# UPS_Input_Board.net
KiCad netlist of a schematic drawn in Altium Designer
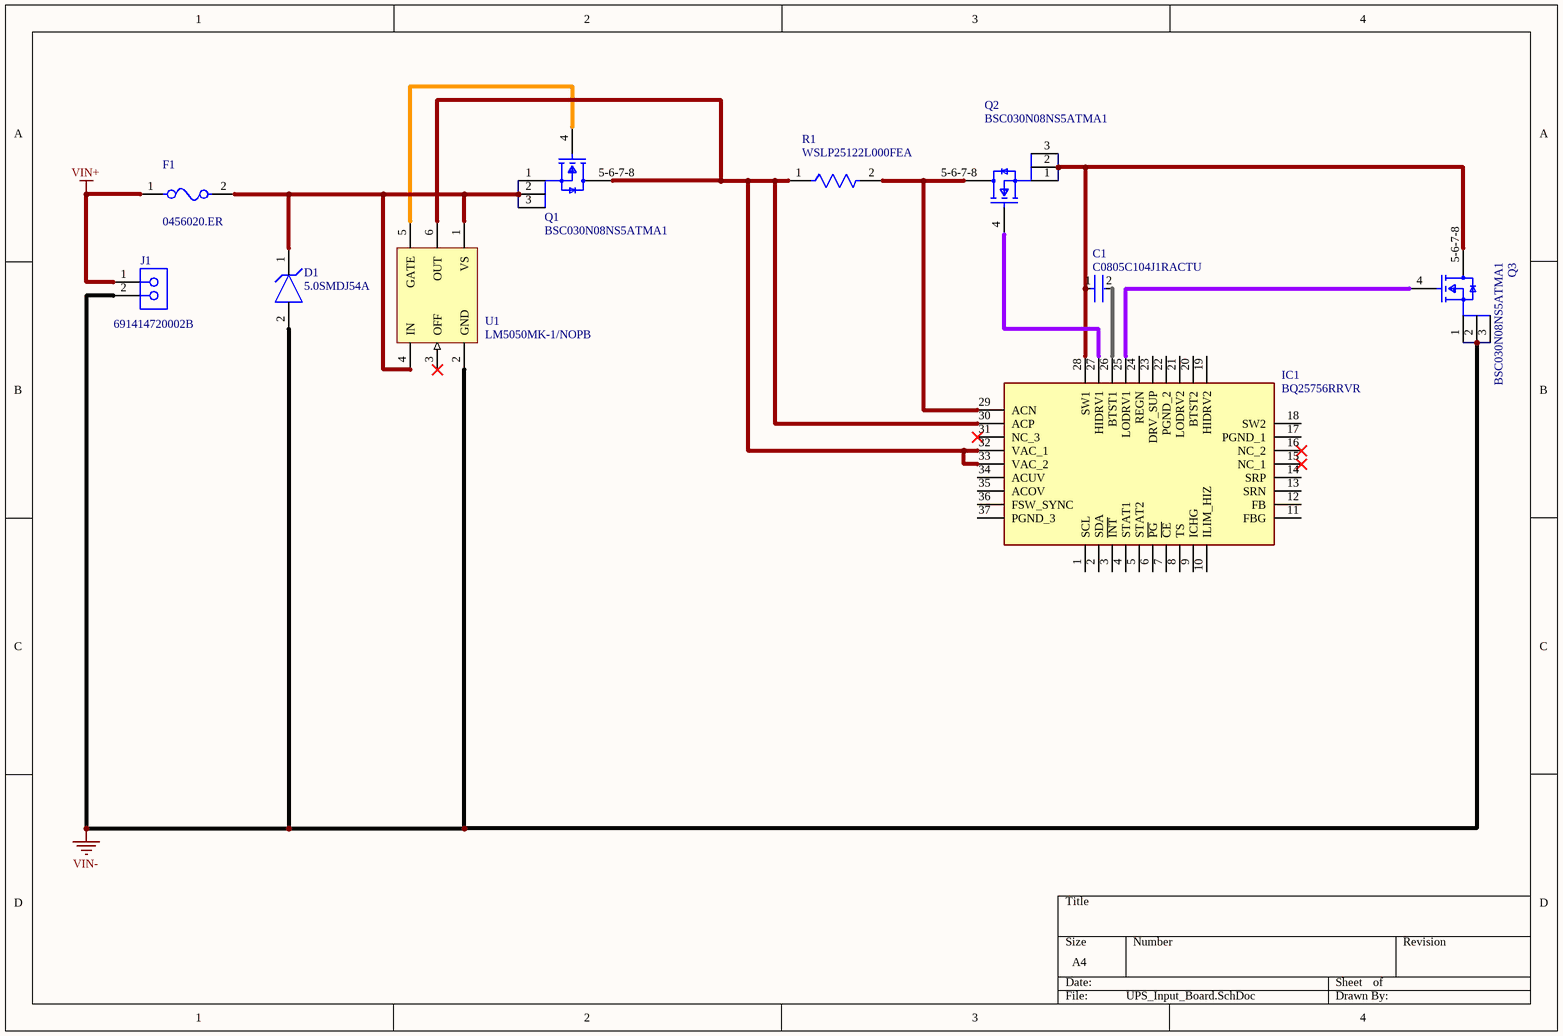
[diagram p0: UPS_Input_Board.SchDoc]

(export (version "E")
  (design (tool "Eeschema 10.0.6"))
  (components
    (comp (ref "C1")
      (value "C0805C104J1RACTU")
      (footprint "FP-C0805C-DN-MFG")
      (description "CAP CER 0.1UF 100V 5% X7R 0805")
      (fields
        (field (name "OCTOPART") "https://octopart.com/c0805c104j1ractu-kemet-10469001")
        (field (name "MANUFACTURER") "KEMET")
      )
      (libsource (lib "Altium Content Vault") (part "b4654b650e69147ec39a6b967a45e02"))
    )
    (comp (ref "D1")
      (value "5.0SMDJ54A")
      (footprint "FP-5_0SMDJ-MFG")
      (description "TVS DIODE 54V 87.1V DO214AB")
      (libsource (lib "Altium Content Vault") (part "673ecd2ea4d7fb87b4005b0cb348b7d"))
    )
    (comp (ref "F1")
      (value "0456020.ER")
      (footprint "FP-0456-MFG")
      (description "FUSE BOARD MNT 20A 125VAC 100VDC")
      (fields
        (field (name "MANUFACTURER") "Littelfuse Inc")
        (field (name "OCTOPART") "https://octopart.com/0456020.er-littelfuse-7502596")
      )
      (libsource (lib "Altium Content Vault") (part "5bcf9b9f640e542cf0359d10258e979"))
    )
    (comp (ref "IC1")
      (value "BQ25756RRVR")
      (footprint "BQ25756RRVR:QFN50P500X600X100-37N-D")
      (description "Integrated Circuit")
      (fields (field (name "MOUSER PART NUMBER") "595-BQ25756RRVR"))
      (libsource (lib "BQ25756RRVR") (part "BQ25756RRVR"))
    )
    (comp (ref "J1")
      (value "691414720002B")
      (footprint "691414720002B")
      (description "Terminal Block, Wtb, 2Way, 28-14Awg Rohs Compliant: Yes")
      (fields (field (name "VOLTAGE") "300V"))
      (libsource (lib "Altium Content Vault") (part "TBL - 1R - 02P - Female"))
    )
    (comp (ref "Q1")
      (value "BSC030N08NS5ATMA1")
      (footprint "FP-PG-TDSON-8-MFG")
      (description "MOSFET N-CH 80V 100A 8TDSON")
      (fields
        (field (name "MANUFACTURER") "Infineon")
        (field (name "OCTOPART") "https://octopart.com/bsc030n08ns5atma1-infineon-52825708")
      )
      (libsource (lib "Altium Content Vault") (part "95ca5d46c4c8fe7d84c4fb5e2abfe3c"))
    )
    (comp (ref "Q2")
      (value "BSC030N08NS5ATMA1")
      (footprint "FP-PG-TDSON-8-MFG")
      (description "MOSFET N-CH 80V 100A 8TDSON")
      (fields
        (field (name "MANUFACTURER") "Infineon")
        (field (name "OCTOPART") "https://octopart.com/bsc030n08ns5atma1-infineon-52825708")
      )
      (libsource (lib "Altium Content Vault") (part "95ca5d46c4c8fe7d84c4fb5e2abfe3c"))
    )
    (comp (ref "Q3")
      (value "BSC030N08NS5ATMA1")
      (footprint "FP-PG-TDSON-8-MFG")
      (description "MOSFET N-CH 80V 100A 8TDSON")
      (fields
        (field (name "MANUFACTURER") "Infineon")
        (field (name "OCTOPART") "https://octopart.com/bsc030n08ns5atma1-infineon-52825708")
      )
      (libsource (lib "Altium Content Vault") (part "95ca5d46c4c8fe7d84c4fb5e2abfe3c"))
    )
    (comp (ref "R1")
      (value "WSLP25122L000FEA")
      (footprint "FP-WSLP2512-0R001-0R0049-MFG")
      (description "RES 0.002 OHM 1% 3W 2512")
      (fields (field (name "TOLERANCE") "1%"))
      (libsource (lib "Altium Content Vault") (part "1029c3af85768c4190bb7ad29bc67b5"))
    )
    (comp (ref "U1")
      (value "LM5050MK-1/NOPB")
      (footprint "DDC0006A_N")
      (description "High Side OR-ing FET Controller, 6-pin TSOT, 1000 Reel")
      (fields (field (name "MANUFACTURER") "Texas Instruments"))
      (libsource (lib "Altium Content Vault") (part "PM-SMPS-LM5050-IL6"))
    )
  )
  (nets
    (net (code "1") (name "Net-(D1-C)") (class "Default")
      (node (ref "D1") (pin "1") (pinfunction "C_1") (pintype "passive"))
      (node (ref "F1") (pin "2") (pinfunction "2_2") (pintype "passive"))
      (node (ref "Q1") (pin "1") (pinfunction "S_1") (pintype "passive"))
      (node (ref "Q1") (pin "2") (pinfunction "S_2") (pintype "passive"))
      (node (ref "Q1") (pin "3") (pinfunction "S_3") (pintype "passive"))
      (node (ref "U1") (pin "1") (pinfunction "VS_1") (pintype "power_in"))
      (node (ref "U1") (pin "4") (pinfunction "IN_4") (pintype "power_in"))
    )
    (net (code "2") (name "Net-(IC1-ACN)") (class "Default")
      (node (ref "IC1") (pin "29") (pinfunction "ACN_29") (pintype "passive"))
      (node (ref "Q2") (pin "5-6-7-8") (pinfunction "D_5-6-7-8") (pintype "passive"))
      (node (ref "R1") (pin "2") (pinfunction "2_2") (pintype "passive"))
    )
    (net (code "3") (name "Net-(IC1-ACP)") (class "Default")
      (node (ref "IC1") (pin "30") (pinfunction "ACP_30") (pintype "passive"))
      (node (ref "IC1") (pin "32") (pinfunction "VAC_1_32") (pintype "passive"))
      (node (ref "IC1") (pin "33") (pinfunction "VAC_2_33") (pintype "passive"))
      (node (ref "Q1") (pin "5-6-7-8") (pinfunction "D_5-6-7-8") (pintype "passive"))
      (node (ref "R1") (pin "1") (pinfunction "1_1") (pintype "passive"))
      (node (ref "U1") (pin "6") (pinfunction "OUT_6") (pintype "power_in"))
    )
    (net (code "4") (name "Net-(IC1-BTST1)") (class "Default")
      (node (ref "C1") (pin "2") (pinfunction "2_2") (pintype "passive"))
      (node (ref "IC1") (pin "26") (pinfunction "BTST1_26") (pintype "passive"))
    )
    (net (code "5") (name "Net-(IC1-HIDRV1)") (class "Default")
      (node (ref "IC1") (pin "27") (pinfunction "HIDRV1_27") (pintype "passive"))
      (node (ref "Q2") (pin "4") (pinfunction "G_4") (pintype "passive"))
    )
    (net (code "6") (name "Net-(IC1-LODRV1)") (class "Default")
      (node (ref "IC1") (pin "25") (pinfunction "LODRV1_25") (pintype "passive"))
      (node (ref "Q3") (pin "4") (pinfunction "G_4") (pintype "passive"))
    )
    (net (code "7") (name "Net-(IC1-SW1)") (class "Default")
      (node (ref "C1") (pin "1") (pinfunction "1_1") (pintype "passive"))
      (node (ref "IC1") (pin "28") (pinfunction "SW1_28") (pintype "passive"))
      (node (ref "Q2") (pin "1") (pinfunction "S_1") (pintype "passive"))
      (node (ref "Q2") (pin "2") (pinfunction "S_2") (pintype "passive"))
      (node (ref "Q2") (pin "3") (pinfunction "S_3") (pintype "passive"))
      (node (ref "Q3") (pin "5-6-7-8") (pinfunction "D_5-6-7-8") (pintype "passive"))
    )
    (net (code "8") (name "Net-(Q1-G)") (class "Default")
      (node (ref "Q1") (pin "4") (pinfunction "G_4") (pintype "passive"))
      (node (ref "U1") (pin "5") (pinfunction "GATE_5") (pintype "power_in"))
    )
    (net (code "9") (name "VIN+") (class "Default")
      (node (ref "F1") (pin "1") (pinfunction "1_1") (pintype "passive"))
      (node (ref "J1") (pin "1") (pinfunction "1_1") (pintype "passive"))
    )
    (net (code "10") (name "VIN-") (class "Default")
      (node (ref "D1") (pin "2") (pinfunction "A_2") (pintype "passive"))
      (node (ref "J1") (pin "2") (pinfunction "2_2") (pintype "passive"))
      (node (ref "Q3") (pin "1") (pinfunction "S_1") (pintype "passive"))
      (node (ref "Q3") (pin "2") (pinfunction "S_2") (pintype "passive"))
      (node (ref "Q3") (pin "3") (pinfunction "S_3") (pintype "passive"))
      (node (ref "U1") (pin "2") (pinfunction "GND_2") (pintype "power_in"))
    )
    (net (code "11") (name "unconnected-(IC1-ACOV-Pad35)") (class "Default")
      (node (ref "IC1") (pin "35") (pinfunction "ACOV_35") (pintype "passive"))
    )
    (net (code "12") (name "unconnected-(IC1-ACUV-Pad34)") (class "Default")
      (node (ref "IC1") (pin "34") (pinfunction "ACUV_34") (pintype "passive"))
    )
    (net (code "13") (name "unconnected-(IC1-BTST2-Pad20)") (class "Default")
      (node (ref "IC1") (pin "20") (pinfunction "BTST2_20") (pintype "passive"))
    )
    (net (code "14") (name "unconnected-(IC1-DRV_SUP-Pad23)") (class "Default")
      (node (ref "IC1") (pin "23") (pinfunction "DRV_SUP_23") (pintype "passive"))
    )
    (net (code "15") (name "unconnected-(IC1-FB-Pad12)") (class "Default")
      (node (ref "IC1") (pin "12") (pinfunction "FB_12") (pintype "passive"))
    )
    (net (code "16") (name "unconnected-(IC1-FBG-Pad11)") (class "Default")
      (node (ref "IC1") (pin "11") (pinfunction "FBG_11") (pintype "passive"))
    )
    (net (code "17") (name "unconnected-(IC1-FSW_SYNC-Pad36)") (class "Default")
      (node (ref "IC1") (pin "36") (pinfunction "FSW_SYNC_36") (pintype "passive"))
    )
    (net (code "18") (name "unconnected-(IC1-HIDRV2-Pad19)") (class "Default")
      (node (ref "IC1") (pin "19") (pinfunction "HIDRV2_19") (pintype "passive"))
    )
    (net (code "19") (name "unconnected-(IC1-ICHG-Pad9)") (class "Default")
      (node (ref "IC1") (pin "9") (pinfunction "ICHG_9") (pintype "passive"))
    )
    (net (code "20") (name "unconnected-(IC1-ILIM_HIZ-Pad10)") (class "Default")
      (node (ref "IC1") (pin "10") (pinfunction "ILIM_HIZ_10") (pintype "passive"))
    )
    (net (code "21") (name "unconnected-(IC1-LODRV2-Pad21)") (class "Default")
      (node (ref "IC1") (pin "21") (pinfunction "LODRV2_21") (pintype "passive"))
    )
    (net (code "22") (name "unconnected-(IC1-NC_1-Pad15)") (class "Default")
      (node (ref "IC1") (pin "15") (pinfunction "NC_1_15") (pintype "passive+no_connect"))
    )
    (net (code "23") (name "unconnected-(IC1-NC_2-Pad16)") (class "Default")
      (node (ref "IC1") (pin "16") (pinfunction "NC_2_16") (pintype "passive+no_connect"))
    )
    (net (code "24") (name "unconnected-(IC1-NC_3-Pad31)") (class "Default")
      (node (ref "IC1") (pin "31") (pinfunction "NC_3_31") (pintype "passive+no_connect"))
    )
    (net (code "25") (name "unconnected-(IC1-PGND_1-Pad17)") (class "Default")
      (node (ref "IC1") (pin "17") (pinfunction "PGND_1_17") (pintype "passive"))
    )
    (net (code "26") (name "unconnected-(IC1-PGND_2-Pad22)") (class "Default")
      (node (ref "IC1") (pin "22") (pinfunction "PGND_2_22") (pintype "passive"))
    )
    (net (code "27") (name "unconnected-(IC1-PGND_3-Pad37)") (class "Default")
      (node (ref "IC1") (pin "37") (pinfunction "PGND_3_37") (pintype "passive"))
    )
    (net (code "28") (name "unconnected-(IC1-REGN-Pad24)") (class "Default")
      (node (ref "IC1") (pin "24") (pinfunction "REGN_24") (pintype "passive"))
    )
    (net (code "29") (name "unconnected-(IC1-SCL-Pad1)") (class "Default")
      (node (ref "IC1") (pin "1") (pinfunction "SCL_1") (pintype "passive"))
    )
    (net (code "30") (name "unconnected-(IC1-SDA-Pad2)") (class "Default")
      (node (ref "IC1") (pin "2") (pinfunction "SDA_2") (pintype "passive"))
    )
    (net (code "31") (name "unconnected-(IC1-SRN-Pad13)") (class "Default")
      (node (ref "IC1") (pin "13") (pinfunction "SRN_13") (pintype "passive"))
    )
    (net (code "32") (name "unconnected-(IC1-SRP-Pad14)") (class "Default")
      (node (ref "IC1") (pin "14") (pinfunction "SRP_14") (pintype "passive"))
    )
    (net (code "33") (name "unconnected-(IC1-STAT1-Pad4)") (class "Default")
      (node (ref "IC1") (pin "4") (pinfunction "STAT1_4") (pintype "passive"))
    )
    (net (code "34") (name "unconnected-(IC1-STAT2-Pad5)") (class "Default")
      (node (ref "IC1") (pin "5") (pinfunction "STAT2_5") (pintype "passive"))
    )
    (net (code "35") (name "unconnected-(IC1-SW2-Pad18)") (class "Default")
      (node (ref "IC1") (pin "18") (pinfunction "SW2_18") (pintype "passive"))
    )
    (net (code "36") (name "unconnected-(IC1-TS-Pad8)") (class "Default")
      (node (ref "IC1") (pin "8") (pinfunction "TS_8") (pintype "passive"))
    )
    (net (code "37") (name "unconnected-(IC1-~{CE}-Pad7)") (class "Default")
      (node (ref "IC1") (pin "7") (pinfunction "~{CE}_7") (pintype "passive"))
    )
    (net (code "38") (name "unconnected-(IC1-~{INT}-Pad3)") (class "Default")
      (node (ref "IC1") (pin "3") (pinfunction "~{INT}_3") (pintype "passive"))
    )
    (net (code "39") (name "unconnected-(IC1-~{PG}-Pad6)") (class "Default")
      (node (ref "IC1") (pin "6") (pinfunction "~{PG}_6") (pintype "passive"))
    )
    (net (code "40") (name "unconnected-(U1-OFF-Pad3)") (class "Default")
      (node (ref "U1") (pin "3") (pinfunction "OFF_3") (pintype "input+no_connect"))
    )
  )
)
